# board.net
KiCad netlist of a schematic drawn in EAGLE
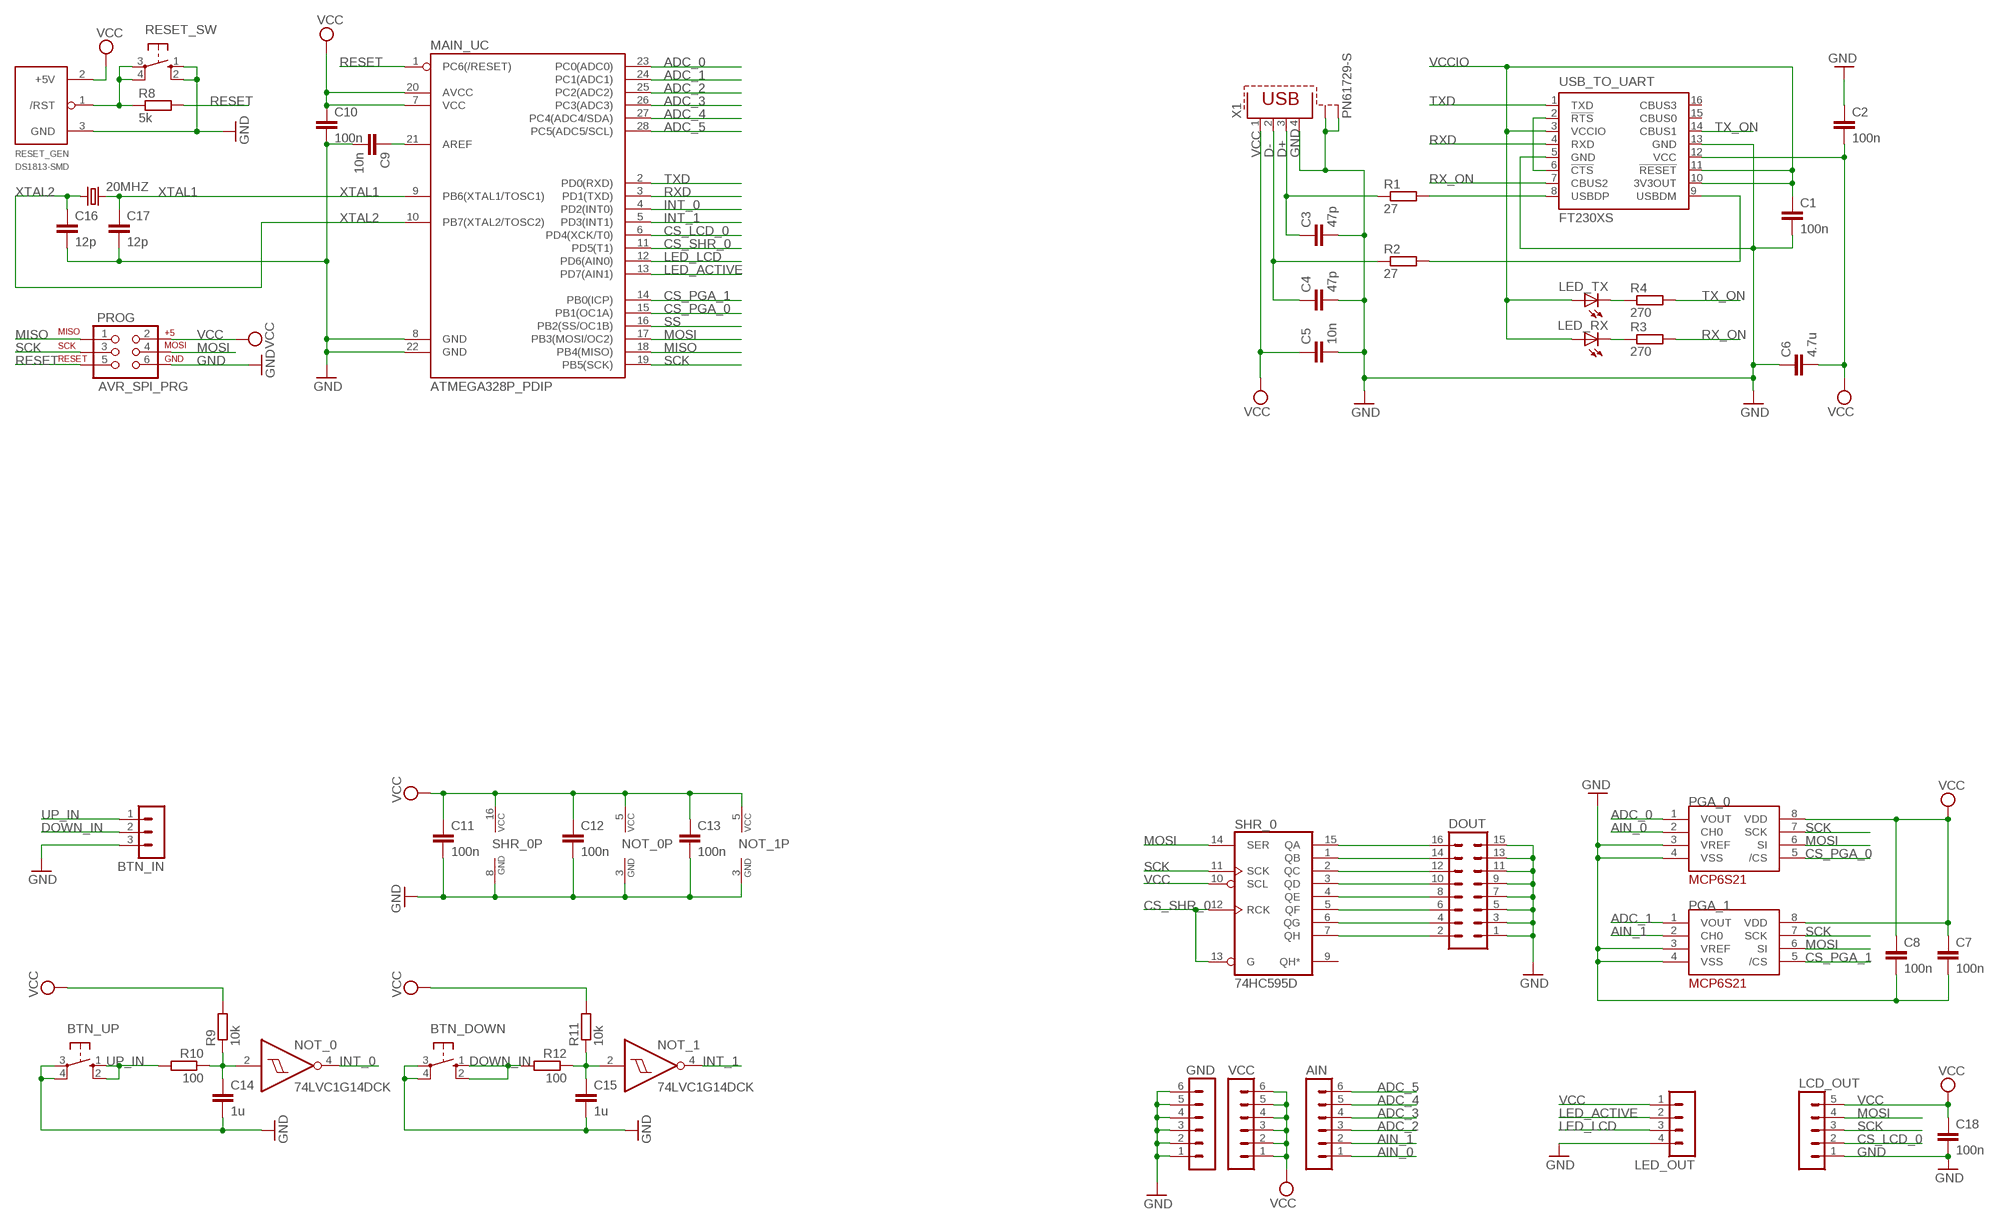
[diagram p0: schematic, sheet 1]

(export (version "E")
  (design (tool "Eeschema 10.0.6"))
  (components
    (comp (ref "20MHZ")
      (value "CRYSTALHC49S")
      (footprint "eagle-import:HC49_S")
      (libsource (lib "eagle-import") (part "CRYSTALHC49S"))
    )
    (comp (ref "AIN")
      (value "MA06-1")
      (footprint "eagle-import:MA06-1")
      (libsource (lib "eagle-import") (part "MA06-1"))
    )
    (comp (ref "BTN_DOWN")
      (value "10-XX")
      (footprint "eagle-import:B3F-10XX")
      (fields (field (name "MPN") "B3F-1000"))
      (libsource (lib "eagle-import") (part "10-XX"))
    )
    (comp (ref "BTN_IN")
      (value "MA03-1")
      (footprint "eagle-import:MA03-1")
      (libsource (lib "eagle-import") (part "MA03-1"))
    )
    (comp (ref "BTN_UP")
      (value "10-XX")
      (footprint "eagle-import:B3F-10XX")
      (fields (field (name "MPN") "B3F-1000"))
      (libsource (lib "eagle-import") (part "10-XX"))
    )
    (comp (ref "C1")
      (value "100n")
      (footprint "eagle-import:C1206")
      (libsource (lib "eagle-import") (part "C-EUC1206"))
    )
    (comp (ref "C2")
      (value "100n")
      (footprint "eagle-import:C1206")
      (libsource (lib "eagle-import") (part "C-EUC1206"))
    )
    (comp (ref "C3")
      (value "47p")
      (footprint "eagle-import:C1206")
      (libsource (lib "eagle-import") (part "C-EUC1206"))
    )
    (comp (ref "C4")
      (value "47p")
      (footprint "eagle-import:C1206")
      (libsource (lib "eagle-import") (part "C-EUC1206"))
    )
    (comp (ref "C5")
      (value "10n")
      (footprint "eagle-import:C1206")
      (libsource (lib "eagle-import") (part "C-EUC1206"))
    )
    (comp (ref "C6")
      (value "4.7u")
      (footprint "eagle-import:C025-025X050")
      (libsource (lib "eagle-import") (part "C-EU025-025X050"))
    )
    (comp (ref "C7")
      (value "100n")
      (footprint "eagle-import:C1206")
      (libsource (lib "eagle-import") (part "C-EUC1206"))
    )
    (comp (ref "C8")
      (value "100n")
      (footprint "eagle-import:C1206")
      (libsource (lib "eagle-import") (part "C-EUC1206"))
    )
    (comp (ref "C9")
      (value "10n")
      (footprint "eagle-import:C1206")
      (libsource (lib "eagle-import") (part "C-EUC1206"))
    )
    (comp (ref "C10")
      (value "100n")
      (footprint "eagle-import:C1206")
      (libsource (lib "eagle-import") (part "C-EUC1206"))
    )
    (comp (ref "C11")
      (value "100n")
      (footprint "eagle-import:C1206")
      (libsource (lib "eagle-import") (part "C-EUC1206"))
    )
    (comp (ref "C12")
      (value "100n")
      (footprint "eagle-import:C1206")
      (libsource (lib "eagle-import") (part "C-EUC1206"))
    )
    (comp (ref "C13")
      (value "100n")
      (footprint "eagle-import:C1206")
      (libsource (lib "eagle-import") (part "C-EUC1206"))
    )
    (comp (ref "C14")
      (value "1u")
      (footprint "eagle-import:C025-024X044")
      (libsource (lib "eagle-import") (part "C-EU025-024X044"))
    )
    (comp (ref "C15")
      (value "1u")
      (footprint "eagle-import:C025-024X044")
      (libsource (lib "eagle-import") (part "C-EU025-024X044"))
    )
    (comp (ref "C16")
      (value "12p")
      (footprint "eagle-import:C1206")
      (libsource (lib "eagle-import") (part "C-EUC1206"))
    )
    (comp (ref "C17")
      (value "12p")
      (footprint "eagle-import:C1206")
      (libsource (lib "eagle-import") (part "C-EUC1206"))
    )
    (comp (ref "C18")
      (value "100n")
      (footprint "eagle-import:C1206")
      (libsource (lib "eagle-import") (part "C-EUC1206"))
    )
    (comp (ref "DOUT")
      (value "MA08-2")
      (footprint "eagle-import:MA08-2")
      (libsource (lib "eagle-import") (part "MA08-2"))
    )
    (comp (ref "GND")
      (value "MA06-1")
      (footprint "eagle-import:MA06-1")
      (libsource (lib "eagle-import") (part "MA06-1"))
    )
    (comp (ref "LCD_OUT")
      (value "MA05-1")
      (footprint "eagle-import:MA05-1")
      (libsource (lib "eagle-import") (part "MA05-1"))
    )
    (comp (ref "LED_OUT")
      (value "MA04-1")
      (footprint "eagle-import:MA04-1")
      (libsource (lib "eagle-import") (part "MA04-1"))
    )
    (comp (ref "LED_RX")
      (value "LEDLD260")
      (footprint "eagle-import:LD260")
      (libsource (lib "eagle-import") (part "LEDLD260"))
    )
    (comp (ref "LED_TX")
      (value "LEDLD260")
      (footprint "eagle-import:LD260")
      (libsource (lib "eagle-import") (part "LEDLD260"))
    )
    (comp (ref "MAIN_UC")
      (value "ATMEGA328P_PDIP")
      (footprint "eagle-import:DIL28-3")
      (libsource (lib "eagle-import") (part "ATMEGA328P_PDIP"))
    )
    (comp (ref "NOT_0")
      (value "74LVC1G14DCK")
      (footprint "eagle-import:SC70-5")
      (libsource (lib "eagle-import") (part "741G14DCKLVC"))
    )
    (comp (ref "NOT_1")
      (value "74LVC1G14DCK")
      (footprint "eagle-import:SC70-5")
      (libsource (lib "eagle-import") (part "741G14DCKLVC"))
    )
    (comp (ref "PGA_0")
      (value "MCP6S21I/SN")
      (footprint "eagle-import:SO-08")
      (libsource (lib "eagle-import") (part "MCP6S21I/SN"))
    )
    (comp (ref "PGA_1")
      (value "MCP6S21I/SN")
      (footprint "eagle-import:SO-08")
      (libsource (lib "eagle-import") (part "MCP6S21I/SN"))
    )
    (comp (ref "PROG")
      (value "AVR_SPI_PRG")
      (footprint "eagle-import:2X3")
      (libsource (lib "eagle-import") (part "AVR_SPI_PRG_6PTH"))
    )
    (comp (ref "R1")
      (value "27")
      (footprint "eagle-import:R1206")
      (libsource (lib "eagle-import") (part "R-EU_R1206"))
    )
    (comp (ref "R2")
      (value "27")
      (footprint "eagle-import:R1206")
      (libsource (lib "eagle-import") (part "R-EU_R1206"))
    )
    (comp (ref "R3")
      (value "270")
      (footprint "eagle-import:R1206")
      (libsource (lib "eagle-import") (part "R-EU_R1206"))
    )
    (comp (ref "R4")
      (value "270")
      (footprint "eagle-import:R1206")
      (libsource (lib "eagle-import") (part "R-EU_R1206"))
    )
    (comp (ref "R8")
      (value "5k")
      (footprint "eagle-import:R1206")
      (libsource (lib "eagle-import") (part "R-EU_R1206"))
    )
    (comp (ref "R9")
      (value "10k")
      (footprint "eagle-import:R1206")
      (libsource (lib "eagle-import") (part "R-EU_R1206"))
    )
    (comp (ref "R10")
      (value "100")
      (footprint "eagle-import:R1206")
      (libsource (lib "eagle-import") (part "R-EU_R1206"))
    )
    (comp (ref "R11")
      (value "10k")
      (footprint "eagle-import:R1206")
      (libsource (lib "eagle-import") (part "R-EU_R1206"))
    )
    (comp (ref "R12")
      (value "100")
      (footprint "eagle-import:R1206")
      (libsource (lib "eagle-import") (part "R-EU_R1206"))
    )
    (comp (ref "RESET_GEN")
      (value "DS1813-SMD")
      (footprint "eagle-import:SOT-23")
      (libsource (lib "eagle-import") (part "DS1813-SMD"))
    )
    (comp (ref "RESET_SW")
      (value "10-XX")
      (footprint "eagle-import:B3F-10XX")
      (fields (field (name "MPN") "B3F-1000"))
      (libsource (lib "eagle-import") (part "10-XX"))
    )
    (comp (ref "SHR_0")
      (value "74HC595D")
      (footprint "eagle-import:SO16")
      (libsource (lib "eagle-import") (part "74595DHC"))
    )
    (comp (ref "USB_TO_UART")
      (value "FT230XS")
      (footprint "eagle-import:SSOP16")
      (libsource (lib "eagle-import") (part "FT230XS"))
    )
    (comp (ref "VCC")
      (value "MA06-1")
      (footprint "eagle-import:MA06-1")
      (libsource (lib "eagle-import") (part "MA06-1"))
    )
    (comp (ref "X1")
      (value "PN61729-S")
      (footprint "eagle-import:PN61729-S")
      (libsource (lib "eagle-import") (part "PN61729-S"))
    )
  )
  (nets
    (net (code "1") (name "/ADC_0") (class "Default")
      (node (ref "MAIN_UC") (pin "23") (pinfunction "PC0(ADC0)_23") (pintype "bidirectional"))
      (node (ref "PGA_0") (pin "1") (pinfunction "VOUT_1") (pintype "bidirectional"))
    )
    (net (code "2") (name "/ADC_1") (class "Default")
      (node (ref "MAIN_UC") (pin "24") (pinfunction "PC1(ADC1)_24") (pintype "bidirectional"))
      (node (ref "PGA_1") (pin "1") (pinfunction "VOUT_1") (pintype "bidirectional"))
    )
    (net (code "3") (name "/ADC_2") (class "Default")
      (node (ref "AIN") (pin "3") (pinfunction "3_3") (pintype "passive"))
      (node (ref "MAIN_UC") (pin "25") (pinfunction "PC2(ADC2)_25") (pintype "bidirectional"))
    )
    (net (code "4") (name "/ADC_3") (class "Default")
      (node (ref "AIN") (pin "4") (pinfunction "4_4") (pintype "passive"))
      (node (ref "MAIN_UC") (pin "26") (pinfunction "PC3(ADC3)_26") (pintype "bidirectional"))
    )
    (net (code "5") (name "/ADC_4") (class "Default")
      (node (ref "AIN") (pin "5") (pinfunction "5_5") (pintype "passive"))
      (node (ref "MAIN_UC") (pin "27") (pinfunction "PC4(ADC4/SDA)_27") (pintype "bidirectional"))
    )
    (net (code "6") (name "/ADC_5") (class "Default")
      (node (ref "AIN") (pin "6") (pinfunction "6_6") (pintype "passive"))
      (node (ref "MAIN_UC") (pin "28") (pinfunction "PC5(ADC5/SCL)_28") (pintype "bidirectional"))
    )
    (net (code "7") (name "/AIN_0") (class "Default")
      (node (ref "AIN") (pin "1") (pinfunction "1_1") (pintype "passive"))
      (node (ref "PGA_0") (pin "2") (pinfunction "CH0_2") (pintype "bidirectional"))
    )
    (net (code "8") (name "/AIN_1") (class "Default")
      (node (ref "AIN") (pin "2") (pinfunction "2_2") (pintype "passive"))
      (node (ref "PGA_1") (pin "2") (pinfunction "CH0_2") (pintype "bidirectional"))
    )
    (net (code "9") (name "/CS_LCD_0") (class "Default")
      (node (ref "LCD_OUT") (pin "2") (pinfunction "2_2") (pintype "passive"))
      (node (ref "MAIN_UC") (pin "6") (pinfunction "PD4(XCK/T0)_6") (pintype "bidirectional"))
    )
    (net (code "10") (name "/CS_PGA_0") (class "Default")
      (node (ref "MAIN_UC") (pin "15") (pinfunction "PB1(OC1A)_15") (pintype "bidirectional"))
      (node (ref "PGA_0") (pin "5") (pinfunction "/CS_5") (pintype "bidirectional"))
    )
    (net (code "11") (name "/CS_PGA_1") (class "Default")
      (node (ref "MAIN_UC") (pin "14") (pinfunction "PB0(ICP)_14") (pintype "bidirectional"))
      (node (ref "PGA_1") (pin "5") (pinfunction "/CS_5") (pintype "bidirectional"))
    )
    (net (code "12") (name "/CS_SHR_0") (class "Default")
      (node (ref "MAIN_UC") (pin "11") (pinfunction "PD5(T1)_11") (pintype "bidirectional"))
      (node (ref "SHR_0") (pin "12") (pinfunction "RCK_12") (pintype "input"))
      (node (ref "SHR_0") (pin "13") (pinfunction "G_13") (pintype "input"))
    )
    (net (code "13") (name "/D+") (class "Default")
      (node (ref "C3") (pin "1") (pinfunction "1_1") (pintype "passive"))
      (node (ref "R1") (pin "1") (pinfunction "1_1") (pintype "passive"))
      (node (ref "X1") (pin "3") (pinfunction "3_3") (pintype "passive"))
    )
    (net (code "14") (name "/D-") (class "Default")
      (node (ref "C4") (pin "1") (pinfunction "1_1") (pintype "passive"))
      (node (ref "R2") (pin "1") (pinfunction "1_1") (pintype "passive"))
      (node (ref "X1") (pin "2") (pinfunction "2_2") (pintype "passive"))
    )
    (net (code "15") (name "/DOWN_IN") (class "Default")
      (node (ref "BTN_DOWN") (pin "1") (pinfunction "S_1") (pintype "passive"))
      (node (ref "BTN_DOWN") (pin "2") (pinfunction "S1_2") (pintype "passive"))
      (node (ref "BTN_IN") (pin "2") (pinfunction "2_2") (pintype "passive"))
      (node (ref "R12") (pin "2") (pinfunction "2_2") (pintype "passive"))
    )
    (net (code "16") (name "/INT_0") (class "Default")
      (node (ref "MAIN_UC") (pin "4") (pinfunction "PD2(INT0)_4") (pintype "bidirectional"))
      (node (ref "NOT_0") (pin "4") (pinfunction "O_4") (pintype "output"))
    )
    (net (code "17") (name "/INT_1") (class "Default")
      (node (ref "MAIN_UC") (pin "5") (pinfunction "PD3(INT1)_5") (pintype "bidirectional"))
      (node (ref "NOT_1") (pin "4") (pinfunction "O_4") (pintype "output"))
    )
    (net (code "18") (name "/LED_ACTIVE") (class "Default")
      (node (ref "LED_OUT") (pin "2") (pinfunction "2_2") (pintype "passive"))
      (node (ref "MAIN_UC") (pin "13") (pinfunction "PD7(AIN1)_13") (pintype "bidirectional"))
    )
    (net (code "19") (name "/LED_LCD") (class "Default")
      (node (ref "LED_OUT") (pin "3") (pinfunction "3_3") (pintype "passive"))
      (node (ref "MAIN_UC") (pin "12") (pinfunction "PD6(AIN0)_12") (pintype "bidirectional"))
    )
    (net (code "20") (name "/MISO") (class "Default")
      (node (ref "MAIN_UC") (pin "18") (pinfunction "PB4(MISO)_18") (pintype "bidirectional"))
      (node (ref "PROG") (pin "1") (pinfunction "1_1") (pintype "passive"))
    )
    (net (code "21") (name "/MOSI") (class "Default")
      (node (ref "LCD_OUT") (pin "4") (pinfunction "4_4") (pintype "passive"))
      (node (ref "MAIN_UC") (pin "17") (pinfunction "PB3(MOSI/OC2)_17") (pintype "bidirectional"))
      (node (ref "PGA_0") (pin "6") (pinfunction "SI_6") (pintype "bidirectional"))
      (node (ref "PGA_1") (pin "6") (pinfunction "SI_6") (pintype "bidirectional"))
      (node (ref "PROG") (pin "4") (pinfunction "4_4") (pintype "passive"))
      (node (ref "SHR_0") (pin "14") (pinfunction "SER_14") (pintype "input"))
    )
    (net (code "22") (name "/RESET") (class "Default")
      (node (ref "MAIN_UC") (pin "1") (pinfunction "PC6(/RESET)_1") (pintype "bidirectional"))
      (node (ref "PROG") (pin "5") (pinfunction "5_5") (pintype "passive"))
      (node (ref "R8") (pin "2") (pinfunction "2_2") (pintype "passive"))
    )
    (net (code "23") (name "/RXD") (class "Default")
      (node (ref "MAIN_UC") (pin "3") (pinfunction "PD1(TXD)_3") (pintype "bidirectional"))
      (node (ref "USB_TO_UART") (pin "4") (pinfunction "RXD_4") (pintype "input"))
    )
    (net (code "24") (name "/RX_ON") (class "Default")
      (node (ref "R3") (pin "2") (pinfunction "2_2") (pintype "passive"))
      (node (ref "USB_TO_UART") (pin "7") (pinfunction "CBUS2_7") (pintype "bidirectional"))
    )
    (net (code "25") (name "/SCK") (class "Default")
      (node (ref "LCD_OUT") (pin "3") (pinfunction "3_3") (pintype "passive"))
      (node (ref "MAIN_UC") (pin "19") (pinfunction "PB5(SCK)_19") (pintype "bidirectional"))
      (node (ref "PGA_0") (pin "7") (pinfunction "SCK_7") (pintype "bidirectional"))
      (node (ref "PGA_1") (pin "7") (pinfunction "SCK_7") (pintype "bidirectional"))
      (node (ref "PROG") (pin "3") (pinfunction "3_3") (pintype "passive"))
      (node (ref "SHR_0") (pin "11") (pinfunction "SCK_11") (pintype "input"))
    )
    (net (code "26") (name "/SS") (class "Default")
      (node (ref "MAIN_UC") (pin "16") (pinfunction "PB2(SS/OC1B)_16") (pintype "bidirectional"))
    )
    (net (code "27") (name "/TXD") (class "Default")
      (node (ref "MAIN_UC") (pin "2") (pinfunction "PD0(RXD)_2") (pintype "bidirectional"))
      (node (ref "USB_TO_UART") (pin "1") (pinfunction "TXD_1") (pintype "output"))
    )
    (net (code "28") (name "/TX_ON") (class "Default")
      (node (ref "R4") (pin "2") (pinfunction "2_2") (pintype "passive"))
      (node (ref "USB_TO_UART") (pin "14") (pinfunction "CBUS1_14") (pintype "bidirectional"))
    )
    (net (code "29") (name "/UP_IN") (class "Default")
      (node (ref "BTN_IN") (pin "1") (pinfunction "1_1") (pintype "passive"))
      (node (ref "BTN_UP") (pin "1") (pinfunction "S_1") (pintype "passive"))
      (node (ref "BTN_UP") (pin "2") (pinfunction "S1_2") (pintype "passive"))
      (node (ref "R10") (pin "2") (pinfunction "2_2") (pintype "passive"))
    )
    (net (code "30") (name "/VCCIO") (class "Default")
      (node (ref "C1") (pin "1") (pinfunction "1_1") (pintype "passive"))
      (node (ref "LED_RX") (pin "A") (pinfunction "A_A") (pintype "passive"))
      (node (ref "LED_TX") (pin "A") (pinfunction "A_A") (pintype "passive"))
      (node (ref "USB_TO_UART") (pin "10") (pinfunction "3V3OUT_10") (pintype "output"))
      (node (ref "USB_TO_UART") (pin "11") (pinfunction "~{RESET}_11") (pintype "input"))
      (node (ref "USB_TO_UART") (pin "3") (pinfunction "VCCIO_3") (pintype "power_in"))
    )
    (net (code "31") (name "/XTAL1") (class "Default")
      (node (ref "20MHZ") (pin "2") (pinfunction "2_2") (pintype "passive"))
      (node (ref "C17") (pin "1") (pinfunction "1_1") (pintype "passive"))
      (node (ref "MAIN_UC") (pin "9") (pinfunction "PB6(XTAL1/TOSC1)_9") (pintype "bidirectional"))
    )
    (net (code "32") (name "/XTAL2") (class "Default")
      (node (ref "20MHZ") (pin "1") (pinfunction "1_1") (pintype "passive"))
      (node (ref "C16") (pin "1") (pinfunction "1_1") (pintype "passive"))
      (node (ref "MAIN_UC") (pin "10") (pinfunction "PB7(XTAL2/TOSC2)_10") (pintype "bidirectional"))
    )
    (net (code "33") (name "GND") (class "Default")
      (node (ref "BTN_DOWN") (pin "3") (pinfunction "P_3") (pintype "passive"))
      (node (ref "BTN_DOWN") (pin "4") (pinfunction "P1_4") (pintype "passive"))
      (node (ref "BTN_IN") (pin "3") (pinfunction "3_3") (pintype "passive"))
      (node (ref "BTN_UP") (pin "3") (pinfunction "P_3") (pintype "passive"))
      (node (ref "BTN_UP") (pin "4") (pinfunction "P1_4") (pintype "passive"))
      (node (ref "C1") (pin "2") (pinfunction "2_2") (pintype "passive"))
      (node (ref "C10") (pin "2") (pinfunction "2_2") (pintype "passive"))
      (node (ref "C11") (pin "2") (pinfunction "2_2") (pintype "passive"))
      (node (ref "C12") (pin "2") (pinfunction "2_2") (pintype "passive"))
      (node (ref "C13") (pin "2") (pinfunction "2_2") (pintype "passive"))
      (node (ref "C14") (pin "2") (pinfunction "2_2") (pintype "passive"))
      (node (ref "C15") (pin "2") (pinfunction "2_2") (pintype "passive"))
      (node (ref "C16") (pin "2") (pinfunction "2_2") (pintype "passive"))
      (node (ref "C17") (pin "2") (pinfunction "2_2") (pintype "passive"))
      (node (ref "C18") (pin "2") (pinfunction "2_2") (pintype "passive"))
      (node (ref "C2") (pin "1") (pinfunction "1_1") (pintype "passive"))
      (node (ref "C3") (pin "2") (pinfunction "2_2") (pintype "passive"))
      (node (ref "C4") (pin "2") (pinfunction "2_2") (pintype "passive"))
      (node (ref "C5") (pin "2") (pinfunction "2_2") (pintype "passive"))
      (node (ref "C6") (pin "1") (pinfunction "1_1") (pintype "passive"))
      (node (ref "C7") (pin "2") (pinfunction "2_2") (pintype "passive"))
      (node (ref "C8") (pin "2") (pinfunction "2_2") (pintype "passive"))
      (node (ref "C9") (pin "2") (pinfunction "2_2") (pintype "passive"))
      (node (ref "DOUT") (pin "1") (pinfunction "1_1") (pintype "passive"))
      (node (ref "DOUT") (pin "11") (pinfunction "11_11") (pintype "passive"))
      (node (ref "DOUT") (pin "13") (pinfunction "13_13") (pintype "passive"))
      (node (ref "DOUT") (pin "15") (pinfunction "15_15") (pintype "passive"))
      (node (ref "DOUT") (pin "3") (pinfunction "3_3") (pintype "passive"))
      (node (ref "DOUT") (pin "5") (pinfunction "5_5") (pintype "passive"))
      (node (ref "DOUT") (pin "7") (pinfunction "7_7") (pintype "passive"))
      (node (ref "DOUT") (pin "9") (pinfunction "9_9") (pintype "passive"))
      (node (ref "GND") (pin "1") (pinfunction "1_1") (pintype "passive"))
      (node (ref "GND") (pin "2") (pinfunction "2_2") (pintype "passive"))
      (node (ref "GND") (pin "3") (pinfunction "3_3") (pintype "passive"))
      (node (ref "GND") (pin "4") (pinfunction "4_4") (pintype "passive"))
      (node (ref "GND") (pin "5") (pinfunction "5_5") (pintype "passive"))
      (node (ref "GND") (pin "6") (pinfunction "6_6") (pintype "passive"))
      (node (ref "LCD_OUT") (pin "1") (pinfunction "1_1") (pintype "passive"))
      (node (ref "LED_OUT") (pin "4") (pinfunction "4_4") (pintype "passive"))
      (node (ref "MAIN_UC") (pin "22") (pinfunction "GND_22") (pintype "bidirectional"))
      (node (ref "MAIN_UC") (pin "8") (pinfunction "GND_8") (pintype "bidirectional"))
      (node (ref "NOT_0") (pin "3") (pinfunction "GND_3") (pintype "power_in"))
      (node (ref "NOT_1") (pin "3") (pinfunction "GND_3") (pintype "power_in"))
      (node (ref "PGA_0") (pin "3") (pinfunction "VREF_3") (pintype "bidirectional"))
      (node (ref "PGA_0") (pin "4") (pinfunction "VSS_4") (pintype "bidirectional"))
      (node (ref "PGA_1") (pin "3") (pinfunction "VREF_3") (pintype "bidirectional"))
      (node (ref "PGA_1") (pin "4") (pinfunction "VSS_4") (pintype "bidirectional"))
      (node (ref "PROG") (pin "6") (pinfunction "6_6") (pintype "passive"))
      (node (ref "RESET_GEN") (pin "3") (pinfunction "GND_3") (pintype "power_in"))
      (node (ref "RESET_SW") (pin "1") (pinfunction "S_1") (pintype "passive"))
      (node (ref "RESET_SW") (pin "2") (pinfunction "S1_2") (pintype "passive"))
      (node (ref "SHR_0") (pin "8") (pinfunction "GND_8") (pintype "power_in"))
      (node (ref "USB_TO_UART") (pin "13") (pinfunction "GND_13") (pintype "power_in"))
      (node (ref "USB_TO_UART") (pin "5") (pinfunction "GND_5") (pintype "power_in"))
      (node (ref "X1") (pin "4") (pinfunction "4_4") (pintype "passive"))
      (node (ref "X1") (pin "S1") (pinfunction "S1_S1") (pintype "passive"))
      (node (ref "X1") (pin "S2") (pinfunction "S2_S2") (pintype "passive"))
    )
    (net (code "34") (name "Net-(LED_RX-C)") (class "Default")
      (node (ref "LED_RX") (pin "K") (pinfunction "C_K") (pintype "passive"))
      (node (ref "R3") (pin "1") (pinfunction "1_1") (pintype "passive"))
    )
    (net (code "35") (name "Net-(LED_TX-C)") (class "Default")
      (node (ref "LED_TX") (pin "K") (pinfunction "C_K") (pintype "passive"))
      (node (ref "R4") (pin "1") (pinfunction "1_1") (pintype "passive"))
    )
    (net (code "36") (name "Net-(MAIN_UC-AREF)") (class "Default")
      (node (ref "C9") (pin "1") (pinfunction "1_1") (pintype "passive"))
      (node (ref "MAIN_UC") (pin "21") (pinfunction "AREF_21") (pintype "bidirectional"))
    )
    (net (code "37") (name "Net-(NOT_0A-I)") (class "Default")
      (node (ref "C14") (pin "1") (pinfunction "1_1") (pintype "passive"))
      (node (ref "NOT_0") (pin "2") (pinfunction "I_2") (pintype "input"))
      (node (ref "R10") (pin "1") (pinfunction "1_1") (pintype "passive"))
      (node (ref "R9") (pin "1") (pinfunction "1_1") (pintype "passive"))
    )
    (net (code "38") (name "Net-(NOT_1A-I)") (class "Default")
      (node (ref "C15") (pin "1") (pinfunction "1_1") (pintype "passive"))
      (node (ref "NOT_1") (pin "2") (pinfunction "I_2") (pintype "input"))
      (node (ref "R11") (pin "1") (pinfunction "1_1") (pintype "passive"))
      (node (ref "R12") (pin "1") (pinfunction "1_1") (pintype "passive"))
    )
    (net (code "39") (name "Net-(RESET_GEN-{slash}RST)") (class "Default")
      (node (ref "R8") (pin "1") (pinfunction "1_1") (pintype "passive"))
      (node (ref "RESET_GEN") (pin "1") (pinfunction "/RST_1") (pintype "passive"))
      (node (ref "RESET_SW") (pin "3") (pinfunction "P_3") (pintype "passive"))
      (node (ref "RESET_SW") (pin "4") (pinfunction "P1_4") (pintype "passive"))
    )
    (net (code "40") (name "Net-(SHR_0A-QA)") (class "Default")
      (node (ref "DOUT") (pin "16") (pinfunction "16_16") (pintype "passive"))
      (node (ref "SHR_0") (pin "15") (pinfunction "QA_15") (pintype "tri_state"))
    )
    (net (code "41") (name "Net-(SHR_0A-QB)") (class "Default")
      (node (ref "DOUT") (pin "14") (pinfunction "14_14") (pintype "passive"))
      (node (ref "SHR_0") (pin "1") (pinfunction "QB_1") (pintype "tri_state"))
    )
    (net (code "42") (name "Net-(SHR_0A-QC)") (class "Default")
      (node (ref "DOUT") (pin "12") (pinfunction "12_12") (pintype "passive"))
      (node (ref "SHR_0") (pin "2") (pinfunction "QC_2") (pintype "tri_state"))
    )
    (net (code "43") (name "Net-(SHR_0A-QD)") (class "Default")
      (node (ref "DOUT") (pin "10") (pinfunction "10_10") (pintype "passive"))
      (node (ref "SHR_0") (pin "3") (pinfunction "QD_3") (pintype "tri_state"))
    )
    (net (code "44") (name "Net-(SHR_0A-QE)") (class "Default")
      (node (ref "DOUT") (pin "8") (pinfunction "8_8") (pintype "passive"))
      (node (ref "SHR_0") (pin "4") (pinfunction "QE_4") (pintype "tri_state"))
    )
    (net (code "45") (name "Net-(SHR_0A-QF)") (class "Default")
      (node (ref "DOUT") (pin "6") (pinfunction "6_6") (pintype "passive"))
      (node (ref "SHR_0") (pin "5") (pinfunction "QF_5") (pintype "tri_state"))
    )
    (net (code "46") (name "Net-(SHR_0A-QG)") (class "Default")
      (node (ref "DOUT") (pin "4") (pinfunction "4_4") (pintype "passive"))
      (node (ref "SHR_0") (pin "6") (pinfunction "QG_6") (pintype "tri_state"))
    )
    (net (code "47") (name "Net-(SHR_0A-QH)") (class "Default")
      (node (ref "DOUT") (pin "2") (pinfunction "2_2") (pintype "passive"))
      (node (ref "SHR_0") (pin "7") (pinfunction "QH_7") (pintype "tri_state"))
    )
    (net (code "48") (name "Net-(USB_TO_UART-USBDM)") (class "Default")
      (node (ref "R2") (pin "2") (pinfunction "2_2") (pintype "passive"))
      (node (ref "USB_TO_UART") (pin "9") (pinfunction "USBDM_9") (pintype "input"))
    )
    (net (code "49") (name "Net-(USB_TO_UART-USBDP)") (class "Default")
      (node (ref "R1") (pin "2") (pinfunction "2_2") (pintype "passive"))
      (node (ref "USB_TO_UART") (pin "8") (pinfunction "USBDP_8") (pintype "input"))
    )
    (net (code "50") (name "Net-(USB_TO_UART-~{CTS})") (class "Default")
      (node (ref "USB_TO_UART") (pin "2") (pinfunction "~{RTS}_2") (pintype "output"))
      (node (ref "USB_TO_UART") (pin "6") (pinfunction "~{CTS}_6") (pintype "input"))
    )
    (net (code "51") (name "VCC") (class "Default")
      (node (ref "C10") (pin "1") (pinfunction "1_1") (pintype "passive"))
      (node (ref "C11") (pin "1") (pinfunction "1_1") (pintype "passive"))
      (node (ref "C12") (pin "1") (pinfunction "1_1") (pintype "passive"))
      (node (ref "C13") (pin "1") (pinfunction "1_1") (pintype "passive"))
      (node (ref "C18") (pin "1") (pinfunction "1_1") (pintype "passive"))
      (node (ref "C2") (pin "2") (pinfunction "2_2") (pintype "passive"))
      (node (ref "C5") (pin "1") (pinfunction "1_1") (pintype "passive"))
      (node (ref "C6") (pin "2") (pinfunction "2_2") (pintype "passive"))
      (node (ref "C7") (pin "1") (pinfunction "1_1") (pintype "passive"))
      (node (ref "C8") (pin "1") (pinfunction "1_1") (pintype "passive"))
      (node (ref "LCD_OUT") (pin "5") (pinfunction "5_5") (pintype "passive"))
      (node (ref "LED_OUT") (pin "1") (pinfunction "1_1") (pintype "passive"))
      (node (ref "MAIN_UC") (pin "20") (pinfunction "AVCC_20") (pintype "bidirectional"))
      (node (ref "MAIN_UC") (pin "7") (pinfunction "VCC_7") (pintype "bidirectional"))
      (node (ref "NOT_0") (pin "5") (pinfunction "VCC_5") (pintype "power_in"))
      (node (ref "NOT_1") (pin "5") (pinfunction "VCC_5") (pintype "power_in"))
      (node (ref "PGA_0") (pin "8") (pinfunction "VDD_8") (pintype "bidirectional"))
      (node (ref "PGA_1") (pin "8") (pinfunction "VDD_8") (pintype "bidirectional"))
      (node (ref "PROG") (pin "2") (pinfunction "2_2") (pintype "passive"))
      (node (ref "R11") (pin "2") (pinfunction "2_2") (pintype "passive"))
      (node (ref "R9") (pin "2") (pinfunction "2_2") (pintype "passive"))
      (node (ref "RESET_GEN") (pin "2") (pinfunction "+5V_2") (pintype "power_in"))
      (node (ref "SHR_0") (pin "10") (pinfunction "SCL_10") (pintype "input"))
      (node (ref "SHR_0") (pin "16") (pinfunction "VCC_16") (pintype "power_in"))
      (node (ref "USB_TO_UART") (pin "12") (pinfunction "VCC_12") (pintype "power_in"))
      (node (ref "VCC") (pin "1") (pinfunction "1_1") (pintype "passive"))
      (node (ref "VCC") (pin "2") (pinfunction "2_2") (pintype "passive"))
      (node (ref "VCC") (pin "3") (pinfunction "3_3") (pintype "passive"))
      (node (ref "VCC") (pin "4") (pinfunction "4_4") (pintype "passive"))
      (node (ref "VCC") (pin "5") (pinfunction "5_5") (pintype "passive"))
      (node (ref "VCC") (pin "6") (pinfunction "6_6") (pintype "passive"))
      (node (ref "X1") (pin "1") (pinfunction "1_1") (pintype "passive"))
    )
    (net (code "52") (name "unconnected-(SHR_0A-QH*-Pad9)") (class "Default")
      (node (ref "SHR_0") (pin "9") (pinfunction "QH*_9") (pintype "tri_state"))
    )
    (net (code "53") (name "unconnected-(USB_TO_UART-CBUS0-Pad15)") (class "Default")
      (node (ref "USB_TO_UART") (pin "15") (pinfunction "CBUS0_15") (pintype "bidirectional"))
    )
    (net (code "54") (name "unconnected-(USB_TO_UART-CBUS3-Pad16)") (class "Default")
      (node (ref "USB_TO_UART") (pin "16") (pinfunction "CBUS3_16") (pintype "bidirectional"))
    )
  )
)
